# MFOS_NT_eurorack_v2.net
KiCad netlist of a schematic drawn in EAGLE
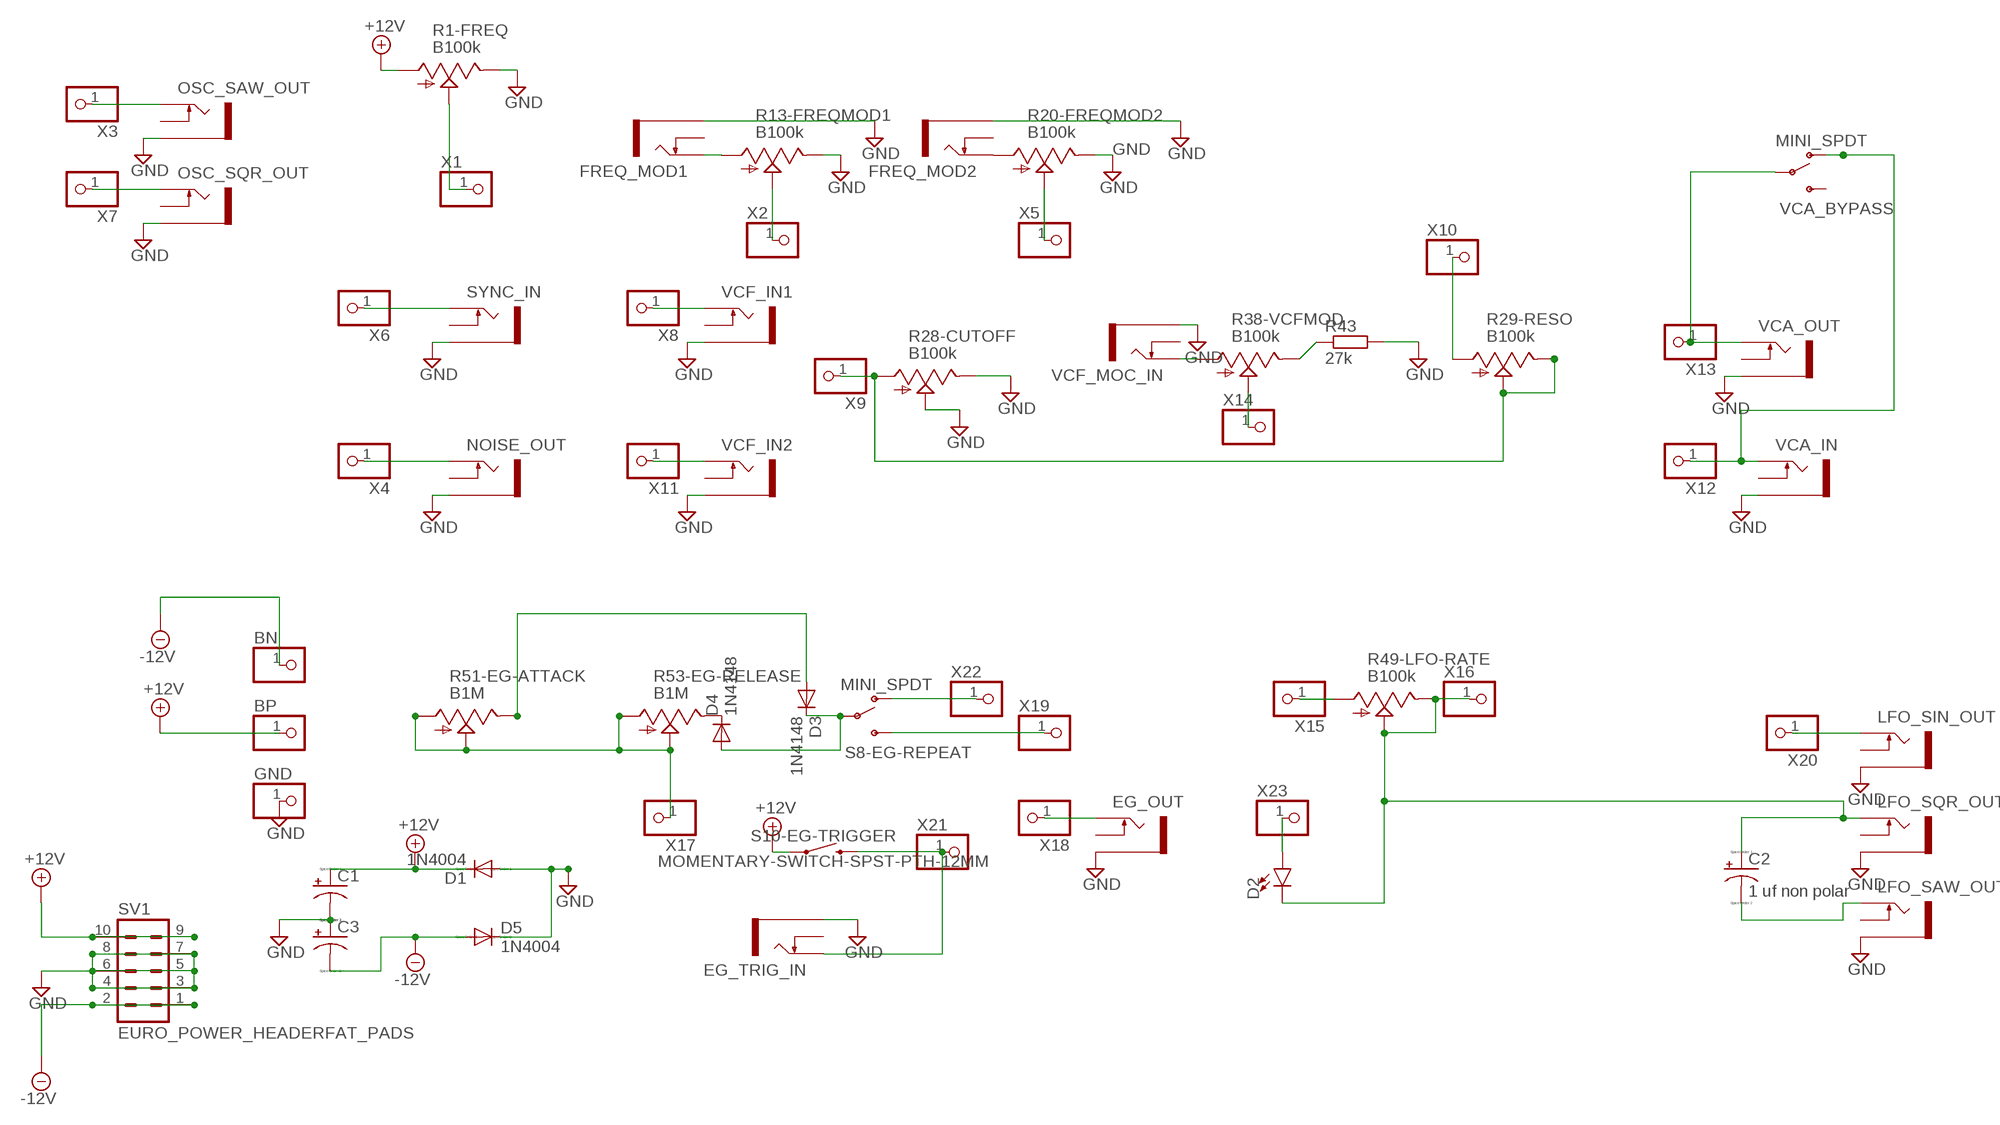
[diagram p0: schematic, sheet 1]

(export (version "E")
  (design (tool "Eeschema 10.0.6"))
  (components
    (comp (ref "BN")
      (value "PINHD-1X1")
      (footprint "eagle-import:1X01")
      (libsource (lib "eagle-import") (part "PINHD-1X1"))
    )
    (comp (ref "BP")
      (value "PINHD-1X1")
      (footprint "eagle-import:1X01")
      (libsource (lib "eagle-import") (part "PINHD-1X1"))
    )
    (comp (ref "C1")
      (value "CPOL-USE2.5-7")
      (footprint "eagle-import:E2,5-7")
      (libsource (lib "eagle-import") (part "CPOL-USE2.5-7"))
    )
    (comp (ref "C2")
      (value "1 uf non polar")
      (footprint "eagle-import:TT2D5L")
      (libsource (lib "eagle-import") (part "CPOL-USTT2D5L"))
    )
    (comp (ref "C3")
      (value "CPOL-USE2.5-7")
      (footprint "eagle-import:E2,5-7")
      (libsource (lib "eagle-import") (part "CPOL-USE2.5-7"))
    )
    (comp (ref "D1")
      (value "1N4004")
      (footprint "eagle-import:DO41-10")
      (libsource (lib "eagle-import") (part "1N4004"))
    )
    (comp (ref "D2")
      (value "LED3MM")
      (footprint "eagle-import:LED_3MM")
      (libsource (lib "eagle-import") (part "LED3MM"))
    )
    (comp (ref "D3")
      (value "1N4148")
      (footprint "eagle-import:DO35-7")
      (libsource (lib "eagle-import") (part "SMALL_DIODEDO35-7"))
    )
    (comp (ref "D4")
      (value "1N4148")
      (footprint "eagle-import:DO35-7")
      (libsource (lib "eagle-import") (part "SMALL_DIODEDO35-7"))
    )
    (comp (ref "D5")
      (value "1N4004")
      (footprint "eagle-import:DO41-10")
      (libsource (lib "eagle-import") (part "1N4004"))
    )
    (comp (ref "EG_OUT")
      (value "THONKICONNNEW")
      (footprint "eagle-import:WQP-PJ301M-12_JACK")
      (libsource (lib "eagle-import") (part "THONKICONNNEW"))
    )
    (comp (ref "EG_TRIG_IN")
      (value "THONKICONNNEW")
      (footprint "eagle-import:WQP-PJ301M-12_JACK")
      (libsource (lib "eagle-import") (part "THONKICONNNEW"))
    )
    (comp (ref "FREQ_MOD1")
      (value "THONKICONNNEW")
      (footprint "eagle-import:WQP-PJ301M-12_JACK")
      (libsource (lib "eagle-import") (part "THONKICONNNEW"))
    )
    (comp (ref "FREQ_MOD2")
      (value "THONKICONNNEW")
      (footprint "eagle-import:WQP-PJ301M-12_JACK")
      (libsource (lib "eagle-import") (part "THONKICONNNEW"))
    )
    (comp (ref "GND")
      (value "PINHD-1X1")
      (footprint "eagle-import:1X01")
      (libsource (lib "eagle-import") (part "PINHD-1X1"))
    )
    (comp (ref "LFO_SAW_OUT")
      (value "THONKICONNNEW")
      (footprint "eagle-import:WQP-PJ301M-12_JACK")
      (libsource (lib "eagle-import") (part "THONKICONNNEW"))
    )
    (comp (ref "LFO_SIN_OUT")
      (value "THONKICONNNEW")
      (footprint "eagle-import:WQP-PJ301M-12_JACK")
      (libsource (lib "eagle-import") (part "THONKICONNNEW"))
    )
    (comp (ref "LFO_SQR_OUT")
      (value "THONKICONNNEW")
      (footprint "eagle-import:WQP-PJ301M-12_JACK")
      (libsource (lib "eagle-import") (part "THONKICONNNEW"))
    )
    (comp (ref "NOISE_OUT")
      (value "THONKICONNNEW")
      (footprint "eagle-import:WQP-PJ301M-12_JACK")
      (libsource (lib "eagle-import") (part "THONKICONNNEW"))
    )
    (comp (ref "OSC_SAW_OUT")
      (value "THONKICONNNEW")
      (footprint "eagle-import:WQP-PJ301M-12_JACK")
      (libsource (lib "eagle-import") (part "THONKICONNNEW"))
    )
    (comp (ref "OSC_SQR_OUT")
      (value "THONKICONNNEW")
      (footprint "eagle-import:WQP-PJ301M-12_JACK")
      (libsource (lib "eagle-import") (part "THONKICONNNEW"))
    )
    (comp (ref "R1-FREQ")
      (value "B100k")
      (footprint "eagle-import:9MM_SNAP-IN_POT")
      (libsource (lib "eagle-import") (part "9MM_SNAP-IN_POT_"))
    )
    (comp (ref "R13-FREQMOD1")
      (value "B100k")
      (footprint "eagle-import:9MM_SNAP-IN_POT")
      (libsource (lib "eagle-import") (part "9MM_SNAP-IN_POT_"))
    )
    (comp (ref "R20-FREQMOD2")
      (value "B100k")
      (footprint "eagle-import:9MM_SNAP-IN_POT")
      (libsource (lib "eagle-import") (part "9MM_SNAP-IN_POT_"))
    )
    (comp (ref "R28-CUTOFF")
      (value "B100k")
      (footprint "eagle-import:9MM_SNAP-IN_POT")
      (libsource (lib "eagle-import") (part "9MM_SNAP-IN_POT_"))
    )
    (comp (ref "R29-RESO")
      (value "B100k")
      (footprint "eagle-import:9MM_SNAP-IN_POT")
      (libsource (lib "eagle-import") (part "9MM_SNAP-IN_POT_"))
    )
    (comp (ref "R38-VCFMOD")
      (value "B100k")
      (footprint "eagle-import:9MM_SNAP-IN_POT")
      (libsource (lib "eagle-import") (part "9MM_SNAP-IN_POT_"))
    )
    (comp (ref "R43")
      (value "27k")
      (footprint "eagle-import:7MM_RESISTOR")
      (libsource (lib "eagle-import") (part "RESISTOR7MM"))
    )
    (comp (ref "R49-LFO-RATE")
      (value "B100k")
      (footprint "eagle-import:9MM_SNAP-IN_POT")
      (libsource (lib "eagle-import") (part "9MM_SNAP-IN_POT_"))
    )
    (comp (ref "R51-EG-ATTACK")
      (value "B1M")
      (footprint "eagle-import:9MM_SNAP-IN_POT")
      (libsource (lib "eagle-import") (part "9MM_SNAP-IN_POT_"))
    )
    (comp (ref "R53-EG-RELEASE")
      (value "B1M")
      (footprint "eagle-import:9MM_SNAP-IN_POT")
      (libsource (lib "eagle-import") (part "9MM_SNAP-IN_POT_"))
    )
    (comp (ref "S8-EG-REPEAT")
      (value "MINI_SPDT")
      (footprint "eagle-import:MINI_SPDT_RIGHTANGLE")
      (libsource (lib "eagle-import") (part "MINI_SPDT"))
    )
    (comp (ref "S10-EG-TRIGGER")
      (value "MOMENTARY-SWITCH-SPST-PTH-12MM")
      (footprint "eagle-import:TACTILE_SWITCH_PTH_12MM")
      (libsource (lib "eagle-import") (part "MOMENTARY-SWITCH-SPST-PTH-12MM"))
    )
    (comp (ref "SV1")
      (value "EURO_POWER_HEADERFAT_PADS")
      (footprint "eagle-import:EURO_PWR_HEADER_FAT")
      (libsource (lib "eagle-import") (part "EURO_POWER_HEADERFAT_PADS"))
    )
    (comp (ref "SYNC_IN")
      (value "THONKICONNNEW")
      (footprint "eagle-import:WQP-PJ301M-12_JACK")
      (libsource (lib "eagle-import") (part "THONKICONNNEW"))
    )
    (comp (ref "VCA_BYPASS")
      (value "MINI_SPDT")
      (footprint "eagle-import:MINI_SPDT_RIGHTANGLE")
      (libsource (lib "eagle-import") (part "MINI_SPDT"))
    )
    (comp (ref "VCA_IN")
      (value "THONKICONNNEW")
      (footprint "eagle-import:WQP-PJ301M-12_JACK")
      (libsource (lib "eagle-import") (part "THONKICONNNEW"))
    )
    (comp (ref "VCA_OUT")
      (value "THONKICONNNEW")
      (footprint "eagle-import:WQP-PJ301M-12_JACK")
      (libsource (lib "eagle-import") (part "THONKICONNNEW"))
    )
    (comp (ref "VCF_IN1")
      (value "THONKICONNNEW")
      (footprint "eagle-import:WQP-PJ301M-12_JACK")
      (libsource (lib "eagle-import") (part "THONKICONNNEW"))
    )
    (comp (ref "VCF_IN2")
      (value "THONKICONNNEW")
      (footprint "eagle-import:WQP-PJ301M-12_JACK")
      (libsource (lib "eagle-import") (part "THONKICONNNEW"))
    )
    (comp (ref "VCF_MOC_IN")
      (value "THONKICONNNEW")
      (footprint "eagle-import:WQP-PJ301M-12_JACK")
      (libsource (lib "eagle-import") (part "THONKICONNNEW"))
    )
    (comp (ref "X1")
      (value "PINHD-1X1")
      (footprint "eagle-import:1X01")
      (libsource (lib "eagle-import") (part "PINHD-1X1"))
    )
    (comp (ref "X2")
      (value "PINHD-1X1")
      (footprint "eagle-import:1X01")
      (libsource (lib "eagle-import") (part "PINHD-1X1"))
    )
    (comp (ref "X3")
      (value "PINHD-1X1")
      (footprint "eagle-import:1X01")
      (libsource (lib "eagle-import") (part "PINHD-1X1"))
    )
    (comp (ref "X4")
      (value "PINHD-1X1")
      (footprint "eagle-import:1X01")
      (libsource (lib "eagle-import") (part "PINHD-1X1"))
    )
    (comp (ref "X5")
      (value "PINHD-1X1")
      (footprint "eagle-import:1X01")
      (libsource (lib "eagle-import") (part "PINHD-1X1"))
    )
    (comp (ref "X6")
      (value "PINHD-1X1")
      (footprint "eagle-import:1X01")
      (libsource (lib "eagle-import") (part "PINHD-1X1"))
    )
    (comp (ref "X7")
      (value "PINHD-1X1")
      (footprint "eagle-import:1X01")
      (libsource (lib "eagle-import") (part "PINHD-1X1"))
    )
    (comp (ref "X8")
      (value "PINHD-1X1")
      (footprint "eagle-import:1X01")
      (libsource (lib "eagle-import") (part "PINHD-1X1"))
    )
    (comp (ref "X9")
      (value "PINHD-1X1")
      (footprint "eagle-import:1X01")
      (libsource (lib "eagle-import") (part "PINHD-1X1"))
    )
    (comp (ref "X10")
      (value "PINHD-1X1")
      (footprint "eagle-import:1X01")
      (libsource (lib "eagle-import") (part "PINHD-1X1"))
    )
    (comp (ref "X11")
      (value "PINHD-1X1")
      (footprint "eagle-import:1X01")
      (libsource (lib "eagle-import") (part "PINHD-1X1"))
    )
    (comp (ref "X12")
      (value "PINHD-1X1")
      (footprint "eagle-import:1X01")
      (libsource (lib "eagle-import") (part "PINHD-1X1"))
    )
    (comp (ref "X13")
      (value "PINHD-1X1")
      (footprint "eagle-import:1X01")
      (libsource (lib "eagle-import") (part "PINHD-1X1"))
    )
    (comp (ref "X14")
      (value "PINHD-1X1")
      (footprint "eagle-import:1X01")
      (libsource (lib "eagle-import") (part "PINHD-1X1"))
    )
    (comp (ref "X15")
      (value "PINHD-1X1")
      (footprint "eagle-import:1X01")
      (libsource (lib "eagle-import") (part "PINHD-1X1"))
    )
    (comp (ref "X16")
      (value "PINHD-1X1")
      (footprint "eagle-import:1X01")
      (libsource (lib "eagle-import") (part "PINHD-1X1"))
    )
    (comp (ref "X17")
      (value "PINHD-1X1")
      (footprint "eagle-import:1X01")
      (libsource (lib "eagle-import") (part "PINHD-1X1"))
    )
    (comp (ref "X18")
      (value "PINHD-1X1")
      (footprint "eagle-import:1X01")
      (libsource (lib "eagle-import") (part "PINHD-1X1"))
    )
    (comp (ref "X19")
      (value "PINHD-1X1")
      (footprint "eagle-import:1X01")
      (libsource (lib "eagle-import") (part "PINHD-1X1"))
    )
    (comp (ref "X20")
      (value "PINHD-1X1")
      (footprint "eagle-import:1X01")
      (libsource (lib "eagle-import") (part "PINHD-1X1"))
    )
    (comp (ref "X21")
      (value "PINHD-1X1")
      (footprint "eagle-import:1X01")
      (libsource (lib "eagle-import") (part "PINHD-1X1"))
    )
    (comp (ref "X22")
      (value "PINHD-1X1")
      (footprint "eagle-import:1X01")
      (libsource (lib "eagle-import") (part "PINHD-1X1"))
    )
    (comp (ref "X23")
      (value "PINHD-1X1")
      (footprint "eagle-import:1X01")
      (libsource (lib "eagle-import") (part "PINHD-1X1"))
    )
  )
  (nets
    (net (code "1") (name "+12V") (class "Default")
      (node (ref "BP") (pin "1") (pinfunction "1_1") (pintype "passive"))
      (node (ref "C1") (pin "+") (pinfunction "+_+") (pintype "passive"))
      (node (ref "D1") (pin "C") (pinfunction "C_C") (pintype "passive"))
      (node (ref "R1-FREQ") (pin "1") (pinfunction "A_1") (pintype "passive"))
      (node (ref "S10-EG-TRIGGER") (pin "1") (pinfunction "1_1") (pintype "passive"))
      (node (ref "SV1") (pin "10") (pinfunction "10_10") (pintype "passive"))
      (node (ref "SV1") (pin "9") (pinfunction "9_9") (pintype "passive"))
    )
    (net (code "2") (name "-12V") (class "Default")
      (node (ref "BN") (pin "1") (pinfunction "1_1") (pintype "passive"))
      (node (ref "C3") (pin "-") (pinfunction "-_-") (pintype "passive"))
      (node (ref "D5") (pin "A") (pinfunction "A_A") (pintype "passive"))
      (node (ref "SV1") (pin "1") (pinfunction "1_1") (pintype "passive"))
      (node (ref "SV1") (pin "2") (pinfunction "2_2") (pintype "passive"))
    )
    (net (code "3") (name "GND") (class "Default")
      (node (ref "C1") (pin "-") (pinfunction "-_-") (pintype "passive"))
      (node (ref "C3") (pin "+") (pinfunction "+_+") (pintype "passive"))
      (node (ref "D1") (pin "A") (pinfunction "A_A") (pintype "passive"))
      (node (ref "D5") (pin "C") (pinfunction "C_C") (pintype "passive"))
      (node (ref "EG_OUT") (pin "P$3_SLEEVE") (pinfunction "SLEEVE_P$3_SLEEVE") (pintype "passive"))
      (node (ref "EG_TRIG_IN") (pin "P$3_SLEEVE") (pinfunction "SLEEVE_P$3_SLEEVE") (pintype "passive"))
      (node (ref "FREQ_MOD1") (pin "P$3_SLEEVE") (pinfunction "SLEEVE_P$3_SLEEVE") (pintype "passive"))
      (node (ref "FREQ_MOD2") (pin "P$3_SLEEVE") (pinfunction "SLEEVE_P$3_SLEEVE") (pintype "passive"))
      (node (ref "GND") (pin "1") (pinfunction "1_1") (pintype "passive"))
      (node (ref "LFO_SAW_OUT") (pin "P$3_SLEEVE") (pinfunction "SLEEVE_P$3_SLEEVE") (pintype "passive"))
      (node (ref "LFO_SIN_OUT") (pin "P$3_SLEEVE") (pinfunction "SLEEVE_P$3_SLEEVE") (pintype "passive"))
      (node (ref "LFO_SQR_OUT") (pin "P$3_SLEEVE") (pinfunction "SLEEVE_P$3_SLEEVE") (pintype "passive"))
      (node (ref "NOISE_OUT") (pin "P$3_SLEEVE") (pinfunction "SLEEVE_P$3_SLEEVE") (pintype "passive"))
      (node (ref "OSC_SAW_OUT") (pin "P$3_SLEEVE") (pinfunction "SLEEVE_P$3_SLEEVE") (pintype "passive"))
      (node (ref "OSC_SQR_OUT") (pin "P$3_SLEEVE") (pinfunction "SLEEVE_P$3_SLEEVE") (pintype "passive"))
      (node (ref "R1-FREQ") (pin "3") (pinfunction "E_3") (pintype "passive"))
      (node (ref "R13-FREQMOD1") (pin "3") (pinfunction "E_3") (pintype "passive"))
      (node (ref "R20-FREQMOD2") (pin "3") (pinfunction "E_3") (pintype "passive"))
      (node (ref "R28-CUTOFF") (pin "2") (pinfunction "S_2") (pintype "passive"))
      (node (ref "R28-CUTOFF") (pin "3") (pinfunction "E_3") (pintype "passive"))
      (node (ref "R43") (pin "2") (pinfunction "2_2") (pintype "passive"))
      (node (ref "SV1") (pin "3") (pinfunction "3_3") (pintype "passive"))
      (node (ref "SV1") (pin "4") (pinfunction "4_4") (pintype "passive"))
      (node (ref "SV1") (pin "5") (pinfunction "5_5") (pintype "passive"))
      (node (ref "SV1") (pin "6") (pinfunction "6_6") (pintype "passive"))
      (node (ref "SV1") (pin "7") (pinfunction "7_7") (pintype "passive"))
      (node (ref "SV1") (pin "8") (pinfunction "8_8") (pintype "passive"))
      (node (ref "SYNC_IN") (pin "P$3_SLEEVE") (pinfunction "SLEEVE_P$3_SLEEVE") (pintype "passive"))
      (node (ref "VCA_IN") (pin "P$3_SLEEVE") (pinfunction "SLEEVE_P$3_SLEEVE") (pintype "passive"))
      (node (ref "VCA_OUT") (pin "P$3_SLEEVE") (pinfunction "SLEEVE_P$3_SLEEVE") (pintype "passive"))
      (node (ref "VCF_IN1") (pin "P$3_SLEEVE") (pinfunction "SLEEVE_P$3_SLEEVE") (pintype "passive"))
      (node (ref "VCF_IN2") (pin "P$3_SLEEVE") (pinfunction "SLEEVE_P$3_SLEEVE") (pintype "passive"))
      (node (ref "VCF_MOC_IN") (pin "P$3_SLEEVE") (pinfunction "SLEEVE_P$3_SLEEVE") (pintype "passive"))
    )
    (net (code "4") (name "Net-(D2-C)") (class "Default")
      (node (ref "C2") (pin "+") (pinfunction "+_+") (pintype "passive"))
      (node (ref "D2") (pin "K") (pinfunction "C_K") (pintype "passive"))
      (node (ref "LFO_SQR_OUT") (pin "P$1_TIP") (pinfunction "TIP_P$1_TIP") (pintype "passive"))
      (node (ref "R49-LFO-RATE") (pin "2") (pinfunction "S_2") (pintype "passive"))
      (node (ref "R49-LFO-RATE") (pin "3") (pinfunction "E_3") (pintype "passive"))
      (node (ref "X16") (pin "1") (pinfunction "1_1") (pintype "passive"))
    )
    (net (code "5") (name "Net-(D2-PadA)") (class "Default")
      (node (ref "D2") (pin "A") (pinfunction "A_A") (pintype "passive"))
      (node (ref "X23") (pin "1") (pinfunction "1_1") (pintype "passive"))
    )
    (net (code "6") (name "Net-(D3-PadC)") (class "Default")
      (node (ref "D3") (pin "C") (pinfunction "C_C") (pintype "passive"))
      (node (ref "D4") (pin "A") (pinfunction "A_A") (pintype "passive"))
      (node (ref "S8-EG-REPEAT") (pin "COMMON") (pinfunction "COMMON_COMMON") (pintype "passive"))
    )
    (net (code "7") (name "Net-(EG_OUT-TIP)") (class "Default")
      (node (ref "EG_OUT") (pin "P$1_TIP") (pinfunction "TIP_P$1_TIP") (pintype "passive"))
      (node (ref "X18") (pin "1") (pinfunction "1_1") (pintype "passive"))
    )
    (net (code "8") (name "Net-(EG_TRIG_IN-TIP)") (class "Default")
      (node (ref "EG_TRIG_IN") (pin "P$1_TIP") (pinfunction "TIP_P$1_TIP") (pintype "passive"))
      (node (ref "S10-EG-TRIGGER") (pin "3") (pinfunction "2_3") (pintype "passive"))
      (node (ref "X21") (pin "1") (pinfunction "1_1") (pintype "passive"))
    )
    (net (code "9") (name "Net-(FREQ_MOD1-TIP)") (class "Default")
      (node (ref "FREQ_MOD1") (pin "P$1_TIP") (pinfunction "TIP_P$1_TIP") (pintype "passive"))
      (node (ref "R13-FREQMOD1") (pin "1") (pinfunction "A_1") (pintype "passive"))
    )
    (net (code "10") (name "Net-(FREQ_MOD2-TIP)") (class "Default")
      (node (ref "FREQ_MOD2") (pin "P$1_TIP") (pinfunction "TIP_P$1_TIP") (pintype "passive"))
      (node (ref "R20-FREQMOD2") (pin "1") (pinfunction "A_1") (pintype "passive"))
    )
    (net (code "11") (name "Net-(LFO_SAW_OUT-TIP)") (class "Default")
      (node (ref "C2") (pin "-") (pinfunction "-_-") (pintype "passive"))
      (node (ref "LFO_SAW_OUT") (pin "P$1_TIP") (pinfunction "TIP_P$1_TIP") (pintype "passive"))
    )
    (net (code "12") (name "Net-(LFO_SIN_OUT-TIP)") (class "Default")
      (node (ref "LFO_SIN_OUT") (pin "P$1_TIP") (pinfunction "TIP_P$1_TIP") (pintype "passive"))
      (node (ref "X20") (pin "1") (pinfunction "1_1") (pintype "passive"))
    )
    (net (code "13") (name "Net-(NOISE_OUT-TIP)") (class "Default")
      (node (ref "NOISE_OUT") (pin "P$1_TIP") (pinfunction "TIP_P$1_TIP") (pintype "passive"))
      (node (ref "X4") (pin "1") (pinfunction "1_1") (pintype "passive"))
    )
    (net (code "14") (name "Net-(OSC_SAW_OUT-TIP)") (class "Default")
      (node (ref "OSC_SAW_OUT") (pin "P$1_TIP") (pinfunction "TIP_P$1_TIP") (pintype "passive"))
      (node (ref "X3") (pin "1") (pinfunction "1_1") (pintype "passive"))
    )
    (net (code "15") (name "Net-(OSC_SQR_OUT-TIP)") (class "Default")
      (node (ref "OSC_SQR_OUT") (pin "P$1_TIP") (pinfunction "TIP_P$1_TIP") (pintype "passive"))
      (node (ref "X7") (pin "1") (pinfunction "1_1") (pintype "passive"))
    )
    (net (code "16") (name "Net-(R1-FREQ-S)") (class "Default")
      (node (ref "R1-FREQ") (pin "2") (pinfunction "S_2") (pintype "passive"))
      (node (ref "X1") (pin "1") (pinfunction "1_1") (pintype "passive"))
    )
    (net (code "17") (name "Net-(R13-FREQMOD1-S)") (class "Default")
      (node (ref "R13-FREQMOD1") (pin "2") (pinfunction "S_2") (pintype "passive"))
      (node (ref "X2") (pin "1") (pinfunction "1_1") (pintype "passive"))
    )
    (net (code "18") (name "Net-(R20-FREQMOD2-S)") (class "Default")
      (node (ref "R20-FREQMOD2") (pin "2") (pinfunction "S_2") (pintype "passive"))
      (node (ref "X5") (pin "1") (pinfunction "1_1") (pintype "passive"))
    )
    (net (code "19") (name "Net-(R28-CUTOFF-A)") (class "Default")
      (node (ref "R28-CUTOFF") (pin "1") (pinfunction "A_1") (pintype "passive"))
      (node (ref "R29-RESO") (pin "2") (pinfunction "S_2") (pintype "passive"))
      (node (ref "R29-RESO") (pin "3") (pinfunction "E_3") (pintype "passive"))
      (node (ref "X9") (pin "1") (pinfunction "1_1") (pintype "passive"))
    )
    (net (code "20") (name "Net-(R29-RESO-A)") (class "Default")
      (node (ref "R29-RESO") (pin "1") (pinfunction "A_1") (pintype "passive"))
      (node (ref "X10") (pin "1") (pinfunction "1_1") (pintype "passive"))
    )
    (net (code "21") (name "Net-(R38-VCFMOD-A)") (class "Default")
      (node (ref "R38-VCFMOD") (pin "1") (pinfunction "A_1") (pintype "passive"))
      (node (ref "VCF_MOC_IN") (pin "P$1_TIP") (pinfunction "TIP_P$1_TIP") (pintype "passive"))
    )
    (net (code "22") (name "Net-(R38-VCFMOD-E)") (class "Default")
      (node (ref "R38-VCFMOD") (pin "3") (pinfunction "E_3") (pintype "passive"))
      (node (ref "R43") (pin "1") (pinfunction "1_1") (pintype "passive"))
    )
    (net (code "23") (name "Net-(R38-VCFMOD-S)") (class "Default")
      (node (ref "R38-VCFMOD") (pin "2") (pinfunction "S_2") (pintype "passive"))
      (node (ref "X14") (pin "1") (pinfunction "1_1") (pintype "passive"))
    )
    (net (code "24") (name "Net-(R49-LFO-RATE-A)") (class "Default")
      (node (ref "R49-LFO-RATE") (pin "1") (pinfunction "A_1") (pintype "passive"))
      (node (ref "X15") (pin "1") (pinfunction "1_1") (pintype "passive"))
    )
    (net (code "25") (name "Net-(R51-EG-ATTACK-A)") (class "Default")
      (node (ref "R51-EG-ATTACK") (pin "1") (pinfunction "A_1") (pintype "passive"))
      (node (ref "R51-EG-ATTACK") (pin "2") (pinfunction "S_2") (pintype "passive"))
      (node (ref "R53-EG-RELEASE") (pin "1") (pinfunction "A_1") (pintype "passive"))
      (node (ref "R53-EG-RELEASE") (pin "2") (pinfunction "S_2") (pintype "passive"))
      (node (ref "X17") (pin "1") (pinfunction "1_1") (pintype "passive"))
    )
    (net (code "26") (name "Net-(R51-EG-ATTACK-E)") (class "Default")
      (node (ref "D3") (pin "A") (pinfunction "A_A") (pintype "passive"))
      (node (ref "R51-EG-ATTACK") (pin "3") (pinfunction "E_3") (pintype "passive"))
    )
    (net (code "27") (name "Net-(R53-EG-RELEASE-E)") (class "Default")
      (node (ref "D4") (pin "C") (pinfunction "C_C") (pintype "passive"))
      (node (ref "R53-EG-RELEASE") (pin "3") (pinfunction "E_3") (pintype "passive"))
    )
    (net (code "28") (name "Net-(S8-EG-REPEAT-O)") (class "Default")
      (node (ref "S8-EG-REPEAT") (pin "UP") (pinfunction "O_UP") (pintype "passive"))
      (node (ref "X22") (pin "1") (pinfunction "1_1") (pintype "passive"))
    )
    (net (code "29") (name "Net-(S8-EG-REPEAT-S)") (class "Default")
      (node (ref "S8-EG-REPEAT") (pin "DOWN") (pinfunction "S_DOWN") (pintype "passive"))
      (node (ref "X19") (pin "1") (pinfunction "1_1") (pintype "passive"))
    )
    (net (code "30") (name "Net-(SYNC_IN-TIP)") (class "Default")
      (node (ref "SYNC_IN") (pin "P$1_TIP") (pinfunction "TIP_P$1_TIP") (pintype "passive"))
      (node (ref "X6") (pin "1") (pinfunction "1_1") (pintype "passive"))
    )
    (net (code "31") (name "Net-(VCA_BYPASS-O)") (class "Default")
      (node (ref "VCA_BYPASS") (pin "UP") (pinfunction "O_UP") (pintype "passive"))
      (node (ref "VCA_IN") (pin "P$1_TIP") (pinfunction "TIP_P$1_TIP") (pintype "passive"))
      (node (ref "X12") (pin "1") (pinfunction "1_1") (pintype "passive"))
    )
    (net (code "32") (name "Net-(VCA_OUT-TIP)") (class "Default")
      (node (ref "VCA_BYPASS") (pin "COMMON") (pinfunction "COMMON_COMMON") (pintype "passive"))
      (node (ref "VCA_OUT") (pin "P$1_TIP") (pinfunction "TIP_P$1_TIP") (pintype "passive"))
      (node (ref "X13") (pin "1") (pinfunction "1_1") (pintype "passive"))
    )
    (net (code "33") (name "Net-(VCF_IN1-TIP)") (class "Default")
      (node (ref "VCF_IN1") (pin "P$1_TIP") (pinfunction "TIP_P$1_TIP") (pintype "passive"))
      (node (ref "X8") (pin "1") (pinfunction "1_1") (pintype "passive"))
    )
    (net (code "34") (name "Net-(VCF_IN2-TIP)") (class "Default")
      (node (ref "VCF_IN2") (pin "P$1_TIP") (pinfunction "TIP_P$1_TIP") (pintype "passive"))
      (node (ref "X11") (pin "1") (pinfunction "1_1") (pintype "passive"))
    )
    (net (code "35") (name "unconnected-(EG_OUT-SWITCH-PadP$2_SWITCH)") (class "Default")
      (node (ref "EG_OUT") (pin "P$2_SWITCH") (pinfunction "SWITCH_P$2_SWITCH") (pintype "passive"))
    )
    (net (code "36") (name "unconnected-(EG_TRIG_IN-SWITCH-PadP$2_SWITCH)") (class "Default")
      (node (ref "EG_TRIG_IN") (pin "P$2_SWITCH") (pinfunction "SWITCH_P$2_SWITCH") (pintype "passive"))
    )
    (net (code "37") (name "unconnected-(FREQ_MOD1-SWITCH-PadP$2_SWITCH)") (class "Default")
      (node (ref "FREQ_MOD1") (pin "P$2_SWITCH") (pinfunction "SWITCH_P$2_SWITCH") (pintype "passive"))
    )
    (net (code "38") (name "unconnected-(FREQ_MOD2-SWITCH-PadP$2_SWITCH)") (class "Default")
      (node (ref "FREQ_MOD2") (pin "P$2_SWITCH") (pinfunction "SWITCH_P$2_SWITCH") (pintype "passive"))
    )
    (net (code "39") (name "unconnected-(LFO_SAW_OUT-SWITCH-PadP$2_SWITCH)") (class "Default")
      (node (ref "LFO_SAW_OUT") (pin "P$2_SWITCH") (pinfunction "SWITCH_P$2_SWITCH") (pintype "passive"))
    )
    (net (code "40") (name "unconnected-(LFO_SIN_OUT-SWITCH-PadP$2_SWITCH)") (class "Default")
      (node (ref "LFO_SIN_OUT") (pin "P$2_SWITCH") (pinfunction "SWITCH_P$2_SWITCH") (pintype "passive"))
    )
    (net (code "41") (name "unconnected-(LFO_SQR_OUT-SWITCH-PadP$2_SWITCH)") (class "Default")
      (node (ref "LFO_SQR_OUT") (pin "P$2_SWITCH") (pinfunction "SWITCH_P$2_SWITCH") (pintype "passive"))
    )
    (net (code "42") (name "unconnected-(NOISE_OUT-SWITCH-PadP$2_SWITCH)") (class "Default")
      (node (ref "NOISE_OUT") (pin "P$2_SWITCH") (pinfunction "SWITCH_P$2_SWITCH") (pintype "passive"))
    )
    (net (code "43") (name "unconnected-(OSC_SAW_OUT-SWITCH-PadP$2_SWITCH)") (class "Default")
      (node (ref "OSC_SAW_OUT") (pin "P$2_SWITCH") (pinfunction "SWITCH_P$2_SWITCH") (pintype "passive"))
    )
    (net (code "44") (name "unconnected-(OSC_SQR_OUT-SWITCH-PadP$2_SWITCH)") (class "Default")
      (node (ref "OSC_SQR_OUT") (pin "P$2_SWITCH") (pinfunction "SWITCH_P$2_SWITCH") (pintype "passive"))
    )
    (net (code "45") (name "unconnected-(SYNC_IN-SWITCH-PadP$2_SWITCH)") (class "Default")
      (node (ref "SYNC_IN") (pin "P$2_SWITCH") (pinfunction "SWITCH_P$2_SWITCH") (pintype "passive"))
    )
    (net (code "46") (name "unconnected-(VCA_BYPASS-S-PadDOWN)") (class "Default")
      (node (ref "VCA_BYPASS") (pin "DOWN") (pinfunction "S_DOWN") (pintype "passive"))
    )
    (net (code "47") (name "unconnected-(VCA_IN-SWITCH-PadP$2_SWITCH)") (class "Default")
      (node (ref "VCA_IN") (pin "P$2_SWITCH") (pinfunction "SWITCH_P$2_SWITCH") (pintype "passive"))
    )
    (net (code "48") (name "unconnected-(VCA_OUT-SWITCH-PadP$2_SWITCH)") (class "Default")
      (node (ref "VCA_OUT") (pin "P$2_SWITCH") (pinfunction "SWITCH_P$2_SWITCH") (pintype "passive"))
    )
    (net (code "49") (name "unconnected-(VCF_IN1-SWITCH-PadP$2_SWITCH)") (class "Default")
      (node (ref "VCF_IN1") (pin "P$2_SWITCH") (pinfunction "SWITCH_P$2_SWITCH") (pintype "passive"))
    )
    (net (code "50") (name "unconnected-(VCF_IN2-SWITCH-PadP$2_SWITCH)") (class "Default")
      (node (ref "VCF_IN2") (pin "P$2_SWITCH") (pinfunction "SWITCH_P$2_SWITCH") (pintype "passive"))
    )
    (net (code "51") (name "unconnected-(VCF_MOC_IN-SWITCH-PadP$2_SWITCH)") (class "Default")
      (node (ref "VCF_MOC_IN") (pin "P$2_SWITCH") (pinfunction "SWITCH_P$2_SWITCH") (pintype "passive"))
    )
  )
)
